# LED_Tester.net
KiCad netlist of a schematic drawn in EAGLE
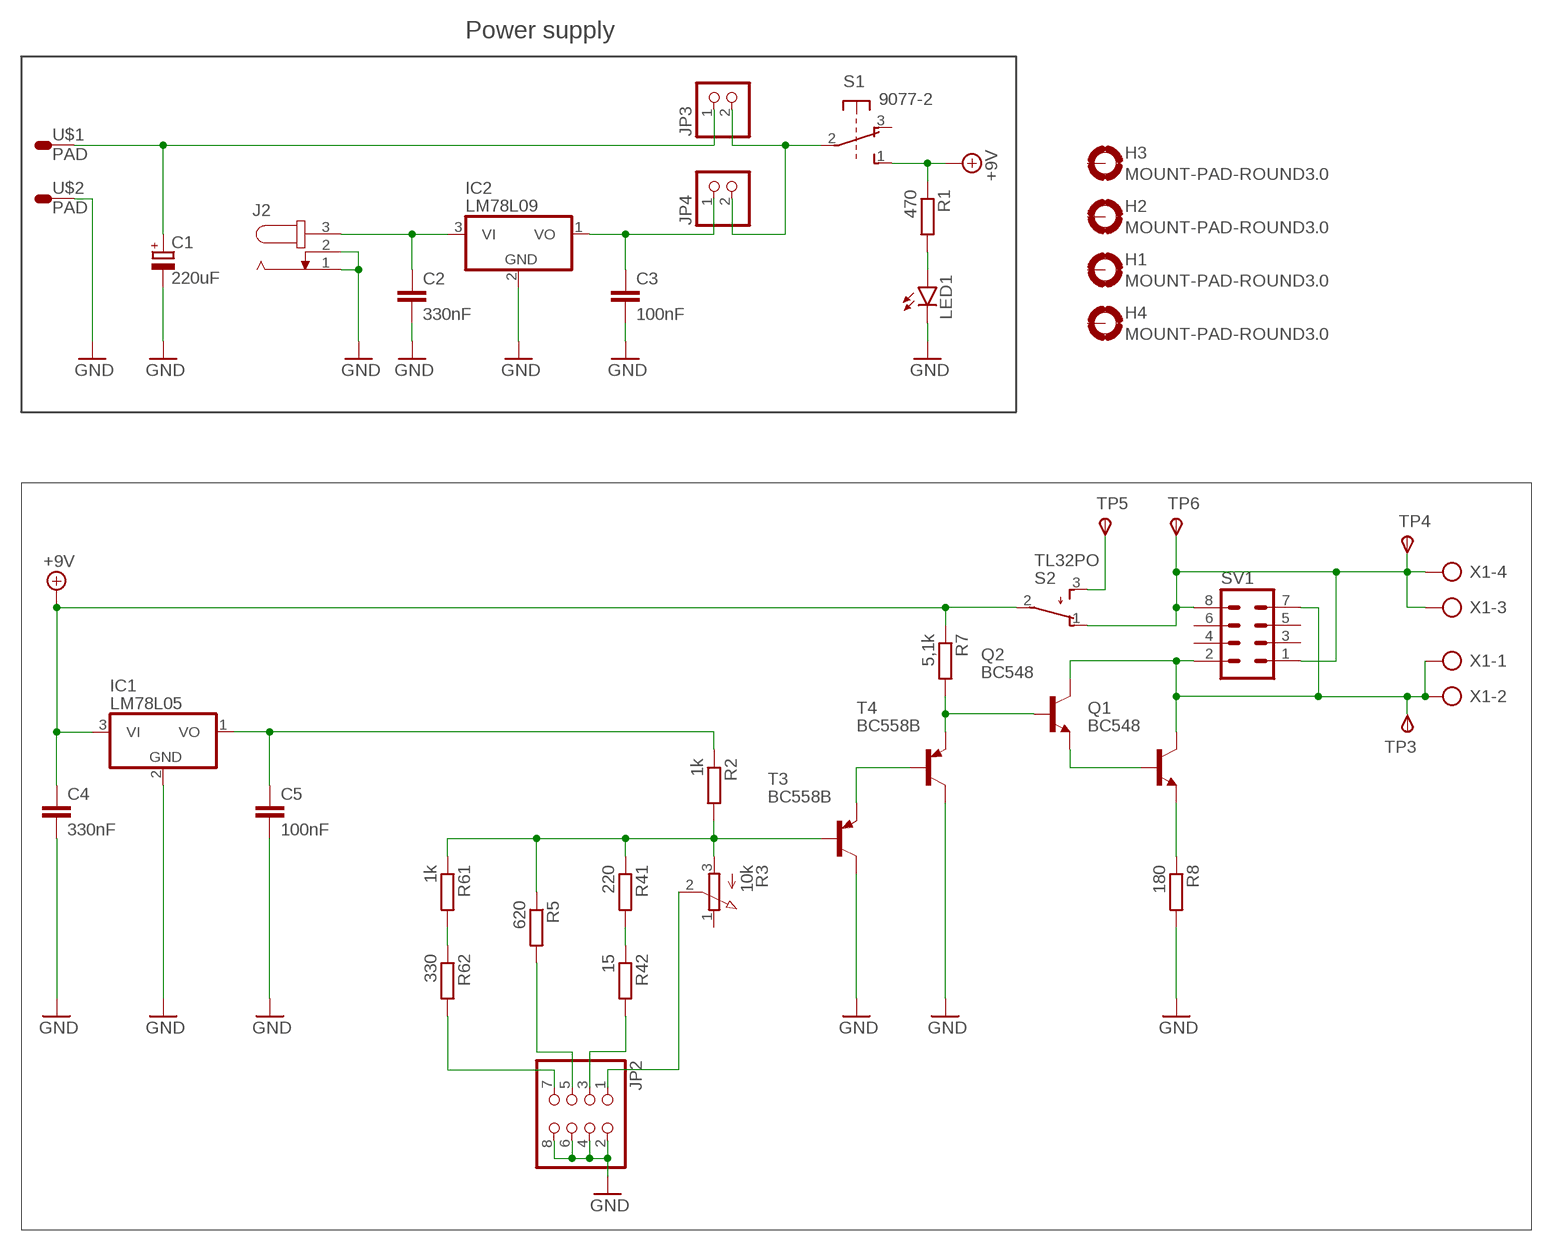
[diagram p0: schematic, sheet 1]

(export (version "E")
  (design (tool "Eeschema 10.0.6"))
  (components
    (comp (ref "C1")
      (value "220uF")
      (footprint "eagle-import:E3,5-8")
      (libsource (lib "eagle-import") (part "CPOL-EUE3.5-8"))
    )
    (comp (ref "C2")
      (value "330nF")
      (footprint "eagle-import:C050-024X044")
      (libsource (lib "eagle-import") (part "C-EU050-024X044"))
    )
    (comp (ref "C3")
      (value "100nF")
      (footprint "eagle-import:C050-024X044")
      (libsource (lib "eagle-import") (part "C-EU050-024X044"))
    )
    (comp (ref "C4")
      (value "330nF")
      (footprint "eagle-import:C050-024X044")
      (libsource (lib "eagle-import") (part "C-EU050-024X044"))
    )
    (comp (ref "C5")
      (value "100nF")
      (footprint "eagle-import:C050-024X044")
      (libsource (lib "eagle-import") (part "C-EU050-024X044"))
    )
    (comp (ref "H1")
      (value "MOUNT-PAD-ROUND3.0")
      (footprint "eagle-import:3,0-PAD")
      (libsource (lib "eagle-import") (part "MOUNT-PAD-ROUND3.0"))
    )
    (comp (ref "H2")
      (value "MOUNT-PAD-ROUND3.0")
      (footprint "eagle-import:3,0-PAD")
      (libsource (lib "eagle-import") (part "MOUNT-PAD-ROUND3.0"))
    )
    (comp (ref "H3")
      (value "MOUNT-PAD-ROUND3.0")
      (footprint "eagle-import:3,0-PAD")
      (libsource (lib "eagle-import") (part "MOUNT-PAD-ROUND3.0"))
    )
    (comp (ref "H4")
      (value "MOUNT-PAD-ROUND3.0")
      (footprint "eagle-import:3,0-PAD")
      (libsource (lib "eagle-import") (part "MOUNT-PAD-ROUND3.0"))
    )
    (comp (ref "IC1")
      (value "LM78L05")
      (footprint "eagle-import:TO92")
      (libsource (lib "eagle-import") (part "LM78LXX"))
    )
    (comp (ref "IC2")
      (value "LM78L09")
      (footprint "eagle-import:TO92")
      (libsource (lib "eagle-import") (part "LM78LXX"))
    )
    (comp (ref "J2")
      (value "JACK-PLUG0")
      (footprint "eagle-import:SPC4077")
      (libsource (lib "eagle-import") (part "JACK-PLUG0"))
    )
    (comp (ref "JP2")
      (value "PINHD-2X4")
      (footprint "eagle-import:2X04")
      (libsource (lib "eagle-import") (part "PINHD-2X4"))
    )
    (comp (ref "JP3")
      (value "PINHD-1X2")
      (footprint "eagle-import:1X02")
      (libsource (lib "eagle-import") (part "PINHD-1X2"))
    )
    (comp (ref "JP4")
      (value "PINHD-1X2")
      (footprint "eagle-import:1X02")
      (libsource (lib "eagle-import") (part "PINHD-1X2"))
    )
    (comp (ref "LED1")
      (value "LED3MM")
      (footprint "eagle-import:LED3MM")
      (libsource (lib "eagle-import") (part "LED3MM"))
    )
    (comp (ref "Q1")
      (value "BC548")
      (footprint "eagle-import:TO92-EBC")
      (libsource (lib "eagle-import") (part "BC548"))
    )
    (comp (ref "Q2")
      (value "BC548")
      (footprint "eagle-import:TO92-EBC")
      (libsource (lib "eagle-import") (part "BC548"))
    )
    (comp (ref "R1")
      (value "470")
      (footprint "eagle-import:0204_7")
      (libsource (lib "eagle-import") (part "R-EU_0204/7"))
    )
    (comp (ref "R2")
      (value "1k")
      (footprint "eagle-import:0207_10")
      (libsource (lib "eagle-import") (part "R-EU_0207/10"))
    )
    (comp (ref "R3")
      (value "10k")
      (footprint "eagle-import:POT_LAY_16_6MM")
      (libsource (lib "eagle-import") (part "POT16/6MM"))
    )
    (comp (ref "R5")
      (value "620")
      (footprint "eagle-import:0204_7")
      (libsource (lib "eagle-import") (part "R-EU_0204/7"))
    )
    (comp (ref "R7")
      (value "5,1k")
      (footprint "eagle-import:0207_10")
      (libsource (lib "eagle-import") (part "R-EU_0207/10"))
    )
    (comp (ref "R8")
      (value "180")
      (footprint "eagle-import:0204_7")
      (libsource (lib "eagle-import") (part "R-EU_0204/7"))
    )
    (comp (ref "R41")
      (value "220")
      (footprint "eagle-import:0204_7")
      (libsource (lib "eagle-import") (part "R-EU_0204/7"))
    )
    (comp (ref "R42")
      (value "15")
      (footprint "eagle-import:0204_7")
      (libsource (lib "eagle-import") (part "R-EU_0204/7"))
    )
    (comp (ref "R61")
      (value "1k")
      (footprint "eagle-import:0204_7")
      (libsource (lib "eagle-import") (part "R-EU_0204/7"))
    )
    (comp (ref "R62")
      (value "330")
      (footprint "eagle-import:0204_7")
      (libsource (lib "eagle-import") (part "R-EU_0204/7"))
    )
    (comp (ref "S1")
      (value "9077-2")
      (footprint "eagle-import:9077-2")
      (libsource (lib "eagle-import") (part "9077-2"))
    )
    (comp (ref "S2")
      (value "TL32PO")
      (footprint "eagle-import:TL3XPO")
      (libsource (lib "eagle-import") (part "TL32PO"))
    )
    (comp (ref "SV1")
      (value "MA04-2")
      (footprint "eagle-import:MA04-2")
      (libsource (lib "eagle-import") (part "MA04-2"))
    )
    (comp (ref "T3")
      (value "BC558B")
      (footprint "eagle-import:TO92-CBE")
      (libsource (lib "eagle-import") (part "-PNP-TO92-CBE2N4126"))
    )
    (comp (ref "T4")
      (value "BC558B")
      (footprint "eagle-import:TO92-CBE")
      (libsource (lib "eagle-import") (part "-PNP-TO92-CBE2N4126"))
    )
    (comp (ref "TP3")
      (value "TPSPAD1-13")
      (footprint "eagle-import:P1-13")
      (libsource (lib "eagle-import") (part "TPSPAD1-13"))
    )
    (comp (ref "TP4")
      (value "TPSPAD1-13")
      (footprint "eagle-import:P1-13")
      (libsource (lib "eagle-import") (part "TPSPAD1-13"))
    )
    (comp (ref "TP5")
      (value "TPSPAD1-13")
      (footprint "eagle-import:P1-13")
      (libsource (lib "eagle-import") (part "TPSPAD1-13"))
    )
    (comp (ref "TP6")
      (value "TPSPAD1-13")
      (footprint "eagle-import:P1-13")
      (libsource (lib "eagle-import") (part "TPSPAD1-13"))
    )
    (comp (ref "U$1")
      (value "PAD")
      (footprint "eagle-import:PAD_BOTTOM")
      (libsource (lib "eagle-import") (part "PAD/BOTTOM"))
    )
    (comp (ref "U$2")
      (value "PAD")
      (footprint "eagle-import:PAD_BOTTOM")
      (libsource (lib "eagle-import") (part "PAD/BOTTOM"))
    )
    (comp (ref "X1")
      (value "AK500/4")
      (footprint "eagle-import:AK500_4")
      (libsource (lib "eagle-import") (part "AK500/4"))
    )
  )
  (nets
    (net (code "1") (name "+9V") (class "Default")
      (node (ref "C4") (pin "1") (pinfunction "1_1") (pintype "passive"))
      (node (ref "IC1") (pin "3") (pinfunction "VI_3") (pintype "input"))
      (node (ref "R1") (pin "1") (pinfunction "1_1") (pintype "passive"))
      (node (ref "R7") (pin "1") (pinfunction "1_1") (pintype "passive"))
      (node (ref "S1") (pin "1") (pinfunction "S_1") (pintype "passive"))
      (node (ref "S2") (pin "2") (pinfunction "P_2") (pintype "passive"))
    )
    (net (code "2") (name "GND") (class "Default")
      (node (ref "C1") (pin "-") (pinfunction "-_-") (pintype "passive"))
      (node (ref "C2") (pin "2") (pinfunction "2_2") (pintype "passive"))
      (node (ref "C3") (pin "2") (pinfunction "2_2") (pintype "passive"))
      (node (ref "C4") (pin "2") (pinfunction "2_2") (pintype "passive"))
      (node (ref "C5") (pin "2") (pinfunction "2_2") (pintype "passive"))
      (node (ref "IC1") (pin "2") (pinfunction "GND_2") (pintype "passive"))
      (node (ref "IC2") (pin "2") (pinfunction "GND_2") (pintype "passive"))
      (node (ref "J2") (pin "1") (pinfunction "1_1") (pintype "passive"))
      (node (ref "J2") (pin "2") (pinfunction "2_2") (pintype "passive"))
      (node (ref "JP2") (pin "2") (pinfunction "2_2") (pintype "passive"))
      (node (ref "JP2") (pin "4") (pinfunction "4_4") (pintype "passive"))
      (node (ref "JP2") (pin "6") (pinfunction "6_6") (pintype "passive"))
      (node (ref "JP2") (pin "8") (pinfunction "8_8") (pintype "passive"))
      (node (ref "LED1") (pin "K") (pinfunction "C_K") (pintype "passive"))
      (node (ref "R8") (pin "2") (pinfunction "2_2") (pintype "passive"))
      (node (ref "T3") (pin "C") (pinfunction "C_C") (pintype "passive"))
      (node (ref "T4") (pin "C") (pinfunction "C_C") (pintype "passive"))
      (node (ref "U$2") (pin "P$1") (pinfunction "S_P$1") (pintype "passive"))
    )
    (net (code "3") (name "Net-(IC1-VO)") (class "Default")
      (node (ref "C5") (pin "1") (pinfunction "1_1") (pintype "passive"))
      (node (ref "IC1") (pin "1") (pinfunction "VO_1") (pintype "passive"))
      (node (ref "R2") (pin "1") (pinfunction "1_1") (pintype "passive"))
    )
    (net (code "4") (name "Net-(IC2-VI)") (class "Default")
      (node (ref "C2") (pin "1") (pinfunction "1_1") (pintype "passive"))
      (node (ref "IC2") (pin "3") (pinfunction "VI_3") (pintype "input"))
      (node (ref "J2") (pin "3") (pinfunction "3_3") (pintype "passive"))
    )
    (net (code "5") (name "Net-(IC2-VO)") (class "Default")
      (node (ref "C3") (pin "1") (pinfunction "1_1") (pintype "passive"))
      (node (ref "IC2") (pin "1") (pinfunction "VO_1") (pintype "passive"))
      (node (ref "JP4") (pin "1") (pinfunction "1_1") (pintype "passive"))
    )
    (net (code "6") (name "Net-(JP2-Pad3)") (class "Default")
      (node (ref "JP2") (pin "3") (pinfunction "3_3") (pintype "passive"))
      (node (ref "R42") (pin "2") (pinfunction "2_2") (pintype "passive"))
    )
    (net (code "7") (name "Net-(JP2-Pad5)") (class "Default")
      (node (ref "JP2") (pin "5") (pinfunction "5_5") (pintype "passive"))
      (node (ref "R5") (pin "2") (pinfunction "2_2") (pintype "passive"))
    )
    (net (code "8") (name "Net-(JP2-Pad7)") (class "Default")
      (node (ref "JP2") (pin "7") (pinfunction "7_7") (pintype "passive"))
      (node (ref "R62") (pin "2") (pinfunction "2_2") (pintype "passive"))
    )
    (net (code "9") (name "Net-(LED1-PadA)") (class "Default")
      (node (ref "LED1") (pin "A") (pinfunction "A_A") (pintype "passive"))
      (node (ref "R1") (pin "2") (pinfunction "2_2") (pintype "passive"))
    )
    (net (code "10") (name "Net-(Q1-PadB)") (class "Default")
      (node (ref "Q1") (pin "B") (pinfunction "B_B") (pintype "passive"))
      (node (ref "Q2") (pin "E") (pinfunction "E_E") (pintype "passive"))
    )
    (net (code "11") (name "Net-(Q1-PadE)") (class "Default")
      (node (ref "Q1") (pin "E") (pinfunction "E_E") (pintype "passive"))
      (node (ref "R8") (pin "1") (pinfunction "1_1") (pintype "passive"))
    )
    (net (code "12") (name "Net-(Q2-PadB)") (class "Default")
      (node (ref "Q2") (pin "B") (pinfunction "B_B") (pintype "passive"))
      (node (ref "R7") (pin "2") (pinfunction "2_2") (pintype "passive"))
      (node (ref "T4") (pin "E") (pinfunction "E_E") (pintype "passive"))
    )
    (net (code "13") (name "Net-(R3-A)") (class "Default")
      (node (ref "R2") (pin "2") (pinfunction "2_2") (pintype "passive"))
      (node (ref "R3") (pin "3") (pinfunction "A_3") (pintype "passive"))
      (node (ref "R41") (pin "1") (pinfunction "1_1") (pintype "passive"))
      (node (ref "R5") (pin "1") (pinfunction "1_1") (pintype "passive"))
      (node (ref "R61") (pin "1") (pinfunction "1_1") (pintype "passive"))
      (node (ref "T3") (pin "B") (pinfunction "B_B") (pintype "passive"))
    )
    (net (code "14") (name "Net-(R3-S)") (class "Default")
      (node (ref "JP2") (pin "1") (pinfunction "1_1") (pintype "passive"))
      (node (ref "R3") (pin "2") (pinfunction "S_2") (pintype "passive"))
    )
    (net (code "15") (name "Net-(R41-Pad2)") (class "Default")
      (node (ref "R41") (pin "2") (pinfunction "2_2") (pintype "passive"))
      (node (ref "R42") (pin "1") (pinfunction "1_1") (pintype "passive"))
    )
    (net (code "16") (name "Net-(R61-Pad2)") (class "Default")
      (node (ref "R61") (pin "2") (pinfunction "2_2") (pintype "passive"))
      (node (ref "R62") (pin "1") (pinfunction "1_1") (pintype "passive"))
    )
    (net (code "17") (name "Net-(S1A-P)") (class "Default")
      (node (ref "JP3") (pin "2") (pinfunction "2_2") (pintype "passive"))
      (node (ref "JP4") (pin "2") (pinfunction "2_2") (pintype "passive"))
      (node (ref "S1") (pin "2") (pinfunction "P_2") (pintype "passive"))
    )
    (net (code "18") (name "Net-(S2-O)") (class "Default")
      (node (ref "S2") (pin "1") (pinfunction "O_1") (pintype "passive"))
      (node (ref "SV1") (pin "1") (pinfunction "1_1") (pintype "passive"))
      (node (ref "SV1") (pin "8") (pinfunction "8_8") (pintype "passive"))
      (node (ref "TP4") (pin "TP") (pinfunction "PP_TP") (pintype "input"))
      (node (ref "TP6") (pin "TP") (pinfunction "PP_TP") (pintype "input"))
      (node (ref "X1") (pin "3") (pinfunction "KL_3") (pintype "passive"))
      (node (ref "X1") (pin "4") (pinfunction "KL_4") (pintype "passive"))
    )
    (net (code "19") (name "Net-(S2-S)") (class "Default")
      (node (ref "S2") (pin "3") (pinfunction "S_3") (pintype "passive"))
      (node (ref "TP5") (pin "TP") (pinfunction "PP_TP") (pintype "input"))
    )
    (net (code "20") (name "Net-(T3-PadE)") (class "Default")
      (node (ref "T3") (pin "E") (pinfunction "E_E") (pintype "passive"))
      (node (ref "T4") (pin "B") (pinfunction "B_B") (pintype "passive"))
    )
    (net (code "21") (name "Net-(TP3-PP)") (class "Default")
      (node (ref "Q1") (pin "C") (pinfunction "C_C") (pintype "passive"))
      (node (ref "Q2") (pin "C") (pinfunction "C_C") (pintype "passive"))
      (node (ref "SV1") (pin "2") (pinfunction "2_2") (pintype "passive"))
      (node (ref "SV1") (pin "7") (pinfunction "7_7") (pintype "passive"))
      (node (ref "TP3") (pin "TP") (pinfunction "PP_TP") (pintype "input"))
      (node (ref "X1") (pin "1") (pinfunction "KL_1") (pintype "passive"))
      (node (ref "X1") (pin "2") (pinfunction "KL_2") (pintype "passive"))
    )
    (net (code "22") (name "Net-(U$1-S)") (class "Default")
      (node (ref "C1") (pin "+") (pinfunction "+_+") (pintype "passive"))
      (node (ref "JP3") (pin "1") (pinfunction "1_1") (pintype "passive"))
      (node (ref "U$1") (pin "P$1") (pinfunction "S_P$1") (pintype "passive"))
    )
    (net (code "23") (name "unconnected-(H1-MOUNT-PadB3,0)") (class "Default")
      (node (ref "H1") (pin "B3,0") (pinfunction "MOUNT_B3,0") (pintype "passive"))
    )
    (net (code "24") (name "unconnected-(H2-MOUNT-PadB3,0)") (class "Default")
      (node (ref "H2") (pin "B3,0") (pinfunction "MOUNT_B3,0") (pintype "passive"))
    )
    (net (code "25") (name "unconnected-(H3-MOUNT-PadB3,0)") (class "Default")
      (node (ref "H3") (pin "B3,0") (pinfunction "MOUNT_B3,0") (pintype "passive"))
    )
    (net (code "26") (name "unconnected-(H4-MOUNT-PadB3,0)") (class "Default")
      (node (ref "H4") (pin "B3,0") (pinfunction "MOUNT_B3,0") (pintype "passive"))
    )
    (net (code "27") (name "unconnected-(R3-E-Pad1)") (class "Default")
      (node (ref "R3") (pin "1") (pinfunction "E_1") (pintype "passive"))
    )
    (net (code "28") (name "unconnected-(S1A-O-Pad3)") (class "Default")
      (node (ref "S1") (pin "3") (pinfunction "O_3") (pintype "passive"))
    )
    (net (code "29") (name "unconnected-(SV1-Pad3)") (class "Default")
      (node (ref "SV1") (pin "3") (pinfunction "3_3") (pintype "passive"))
    )
    (net (code "30") (name "unconnected-(SV1-Pad4)") (class "Default")
      (node (ref "SV1") (pin "4") (pinfunction "4_4") (pintype "passive"))
    )
    (net (code "31") (name "unconnected-(SV1-Pad5)") (class "Default")
      (node (ref "SV1") (pin "5") (pinfunction "5_5") (pintype "passive"))
    )
    (net (code "32") (name "unconnected-(SV1-Pad6)") (class "Default")
      (node (ref "SV1") (pin "6") (pinfunction "6_6") (pintype "passive"))
    )
  )
)
